# Fri3d_2026_Keeb_01.net
KiCad netlist of a schematic drawn in Altium Designer
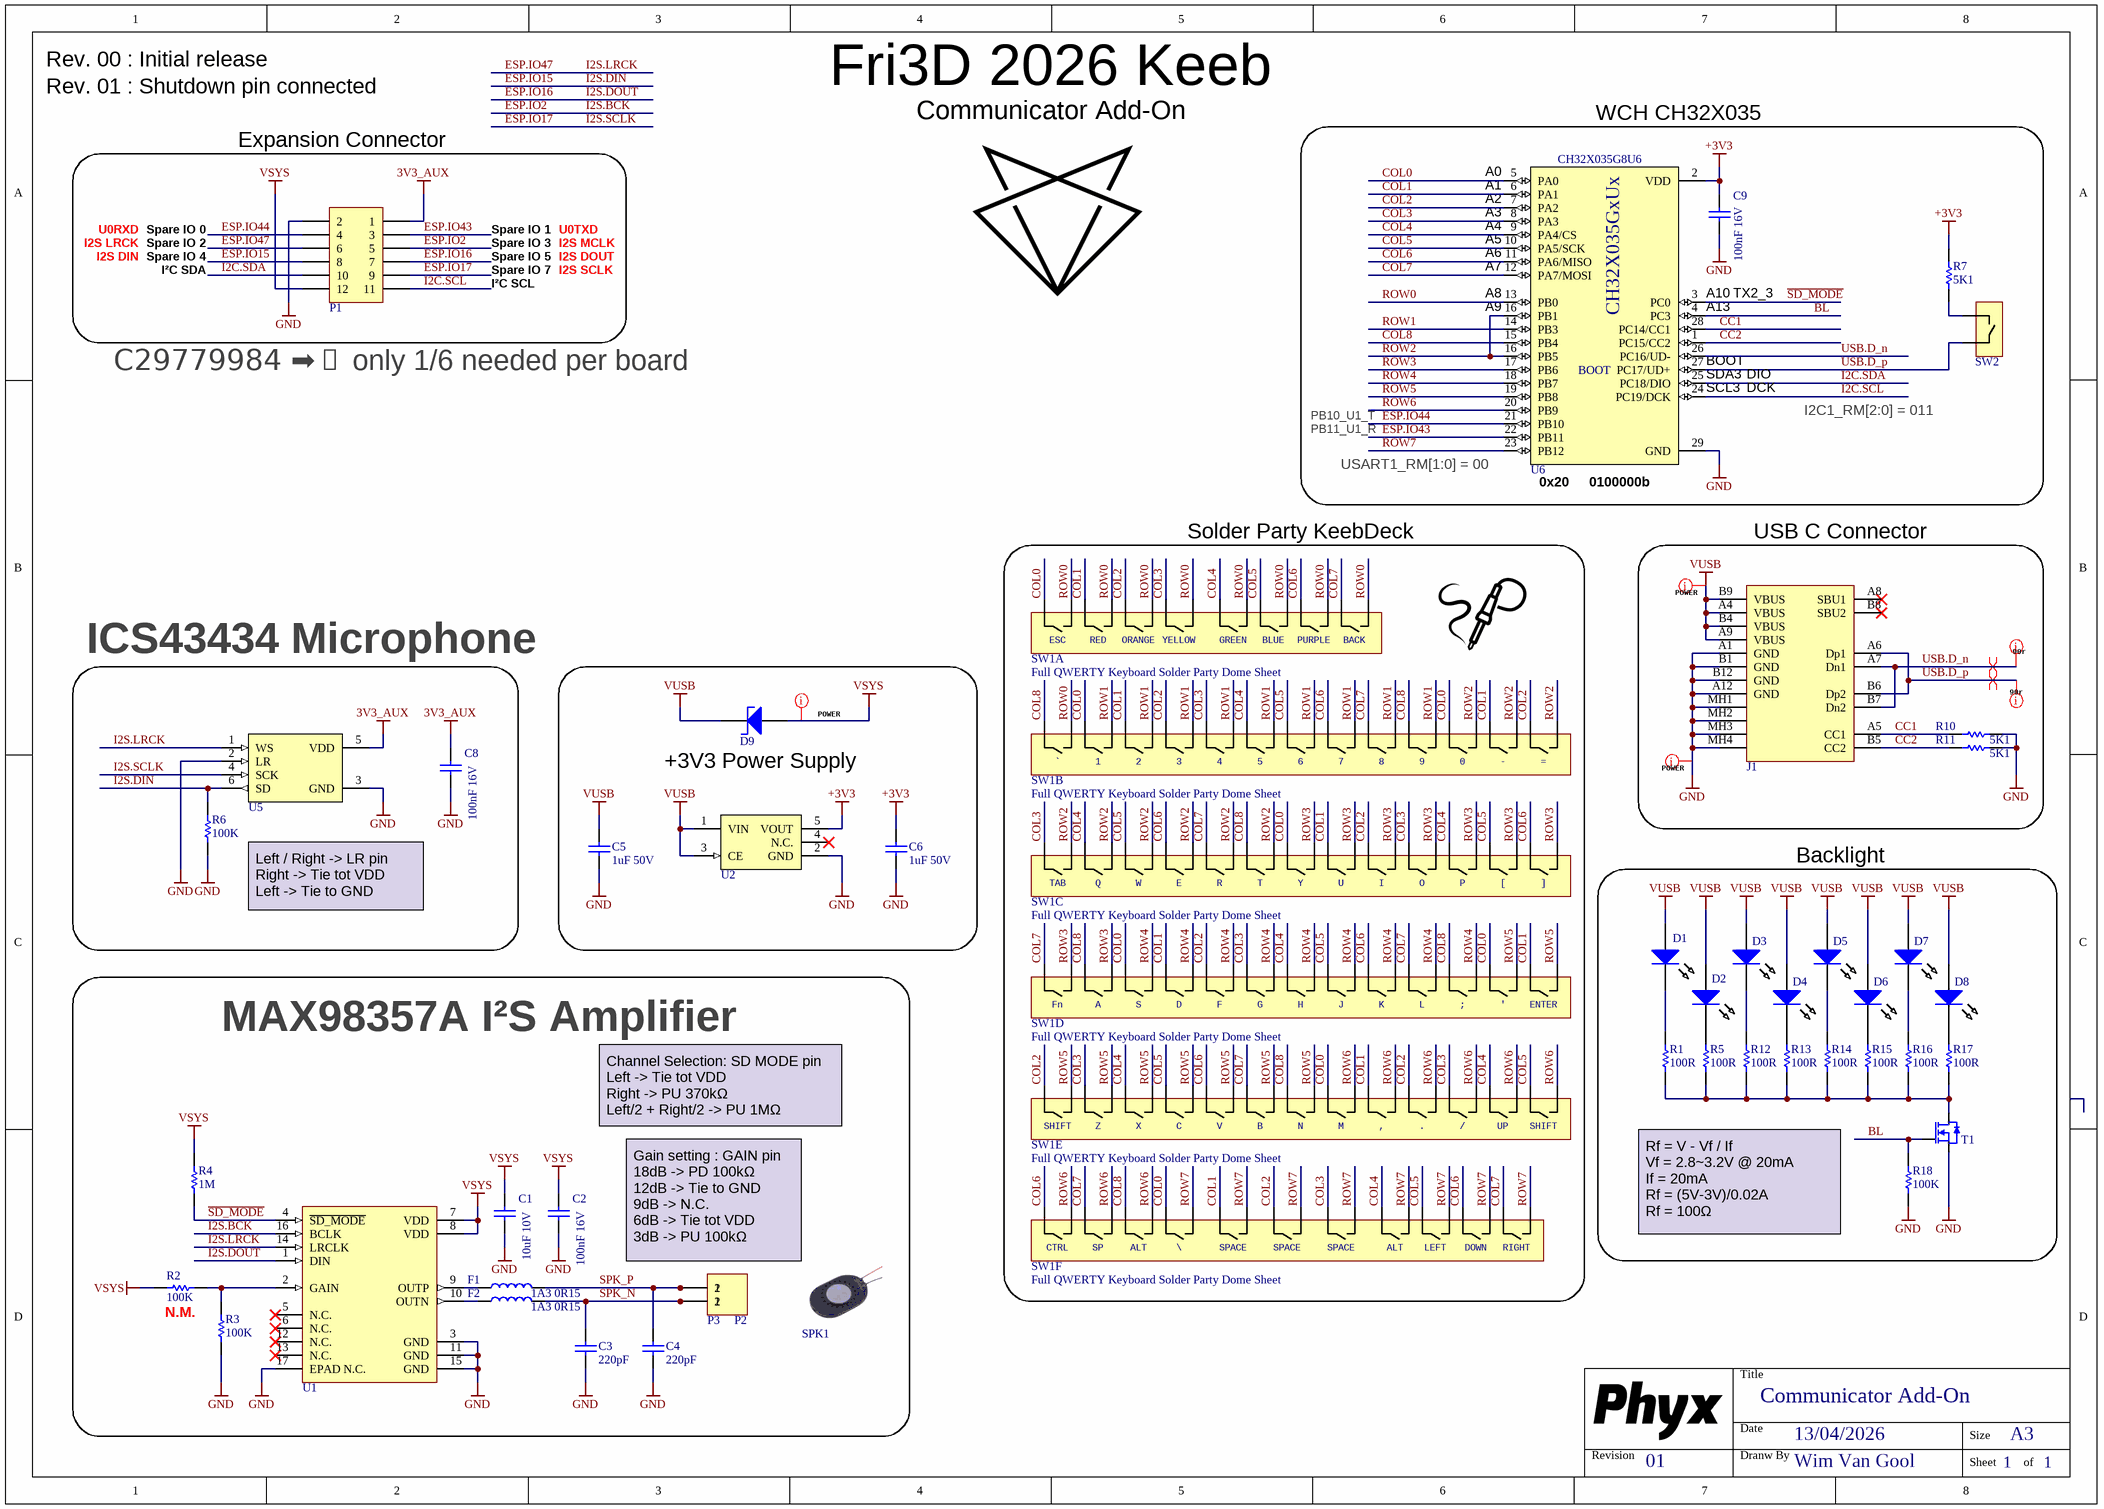
[diagram p0: Fri3d_2026_Keeb_01.SchDoc]

(export (version "E")
  (design (tool "Eeschema 10.0.6"))
  (components
    (comp (ref "C1")
      (value "10uF 10V")
      (footprint "C0805_N")
      (description "Capacitor Ceramic")
      (fields (field (name "Comment") "CAP_CERAMIC"))
      (libsource (lib "Phyx_Components") (part "CAP_CERAMIC"))
    )
    (comp (ref "C2")
      (value "100nF 16V")
      (footprint "C0603_N")
      (description "Capacitor Ceramic")
      (libsource (lib "Phyx_Components") (part "CAP_CERAMIC"))
    )
    (comp (ref "C3")
      (value "220pF")
      (footprint "C0603_N")
      (description "Capacitor Ceramic")
      (fields (field (name "Comment") "CAP_CERAMIC"))
      (libsource (lib "Phyx_Components") (part "CAP_CERAMIC"))
    )
    (comp (ref "C4")
      (value "220pF")
      (footprint "C0603_N")
      (description "Capacitor Ceramic")
      (fields (field (name "Comment") "CAP_CERAMIC"))
      (libsource (lib "Phyx_Components") (part "CAP_CERAMIC"))
    )
    (comp (ref "C5")
      (value "1uF 50V")
      (footprint "C0603_N")
      (description "Capacitor Ceramic")
      (fields (field (name "Comment") "CAP_CERAMIC"))
      (libsource (lib "Phyx_Components") (part "CAP_CERAMIC"))
    )
    (comp (ref "C6")
      (value "1uF 50V")
      (footprint "C0603_N")
      (description "Capacitor Ceramic")
      (fields (field (name "Comment") "CAP_CERAMIC"))
      (libsource (lib "Phyx_Components") (part "CAP_CERAMIC"))
    )
    (comp (ref "C8")
      (value "100nF 16V")
      (footprint "C0603_N")
      (description "Capacitor Ceramic")
      (libsource (lib "Phyx_Components") (part "CAP_CERAMIC"))
    )
    (comp (ref "C9")
      (value "100nF 16V")
      (footprint "C0603_N")
      (description "Capacitor Ceramic")
      (libsource (lib "Phyx_Components") (part "CAP_CERAMIC"))
    )
    (comp (ref "D1")
      (value "Side emitting Cool White LED 3.0V 30mA 120° 2900mcd")
      (footprint "LITE_LTW-010DCG")
      (description "=Description")
      (libsource (lib "Phyx_Components") (part "LED_WHITE"))
    )
    (comp (ref "D2")
      (value "Side emitting Cool White LED 3.0V 30mA 120° 2900mcd")
      (footprint "LITE_LTW-010DCG")
      (description "=Description")
      (libsource (lib "Phyx_Components") (part "LED_WHITE"))
    )
    (comp (ref "D3")
      (value "Side emitting Cool White LED 3.0V 30mA 120° 2900mcd")
      (footprint "LITE_LTW-010DCG")
      (description "=Description")
      (libsource (lib "Phyx_Components") (part "LED_WHITE"))
    )
    (comp (ref "D4")
      (value "Side emitting Cool White LED 3.0V 30mA 120° 2900mcd")
      (footprint "LITE_LTW-010DCG")
      (description "=Description")
      (libsource (lib "Phyx_Components") (part "LED_WHITE"))
    )
    (comp (ref "D5")
      (value "Side emitting Cool White LED 3.0V 30mA 120° 2900mcd")
      (footprint "LITE_LTW-010DCG")
      (description "=Description")
      (libsource (lib "Phyx_Components") (part "LED_WHITE"))
    )
    (comp (ref "D6")
      (value "Side emitting Cool White LED 3.0V 30mA 120° 2900mcd")
      (footprint "LITE_LTW-010DCG")
      (description "=Description")
      (libsource (lib "Phyx_Components") (part "LED_WHITE"))
    )
    (comp (ref "D7")
      (value "Side emitting Cool White LED 3.0V 30mA 120° 2900mcd")
      (footprint "LITE_LTW-010DCG")
      (description "=Description")
      (libsource (lib "Phyx_Components") (part "LED_WHITE"))
    )
    (comp (ref "D8")
      (value "Side emitting Cool White LED 3.0V 30mA 120° 2900mcd")
      (footprint "LITE_LTW-010DCG")
      (description "=Description")
      (libsource (lib "Phyx_Components") (part "LED_WHITE"))
    )
    (comp (ref "D9")
      (value "CUS10S30 Schottky Power Rectifier, 1A, 30V")
      (footprint "SOD-323_AC")
      (description "=Description")
      (libsource (lib "Phyx_Components") (part "Schottky_AC"))
    )
    (comp (ref "F1")
      (value "1A3 0R15")
      (footprint "L0603")
      (fields (field (name "Comment") "BLM18KG601SN1D"))
      (libsource (lib "Phyx_Components") (part "FERRITE"))
    )
    (comp (ref "F2")
      (value "1A3 0R15")
      (footprint "L0603")
      (fields (field (name "Comment") "BLM18KG601SN1D"))
      (libsource (lib "Phyx_Components") (part "FERRITE"))
    )
    (comp (ref "J1")
      (value "USB 2.0 C Reversible Receptacle Horizontal full SMD")
      (footprint "XUNPU-TYPEC-304S-ACP16")
      (libsource (lib "Phyx_Components") (part "USB_C_16_4"))
    )
    (comp (ref "P1")
      (value "Header 6X2")
      (footprint "HDR2X6")
      (libsource (lib "Phyx_Components") (part "Header 6X2"))
    )
    (comp (ref "P2")
      (value "SHETIME WAF02-T1T1-2021-D")
      (footprint "SHE_WAF02-T1T1-2021-D")
      (libsource (lib "Phyx_Components") (part "Header 2"))
    )
    (comp (ref "P3") (value "Header 2 RA") (footprint "HDR1X2_RA") (libsource (lib "") (part "Header 2_1")))
    (comp (ref "R1")
      (value "100R")
      (footprint "R0603_N")
      (fields (field (name "Comment") "RESISTOR"))
      (libsource (lib "Phyx_Components") (part "RESISTOR"))
    )
    (comp (ref "R2")
      (value "100K")
      (footprint "R0603_N")
      (fields (field (name "Comment") "RESISTOR"))
      (libsource (lib "Phyx_Components") (part "RESISTOR"))
    )
    (comp (ref "R3")
      (value "100K")
      (footprint "R0603_N")
      (fields (field (name "Comment") "RESISTOR"))
      (libsource (lib "Phyx_Components") (part "RESISTOR"))
    )
    (comp (ref "R4")
      (value "1M")
      (footprint "R0603_N")
      (fields (field (name "Comment") "RESISTOR"))
      (libsource (lib "Phyx_Components") (part "RESISTOR"))
    )
    (comp (ref "R5")
      (value "100R")
      (footprint "R0603_N")
      (fields (field (name "Comment") "RESISTOR"))
      (libsource (lib "Phyx_Components") (part "RESISTOR"))
    )
    (comp (ref "R6")
      (value "100K")
      (footprint "R0603_N")
      (fields (field (name "Comment") "RESISTOR"))
      (libsource (lib "Phyx_Components") (part "RESISTOR"))
    )
    (comp (ref "R7")
      (value "5K1")
      (footprint "R0603_N")
      (fields (field (name "Comment") "RESISTOR"))
      (libsource (lib "Phyx_Components") (part "RESISTOR"))
    )
    (comp (ref "R10")
      (value "5K1")
      (footprint "R0603_N")
      (fields (field (name "Comment") "RESISTOR"))
      (libsource (lib "Phyx_Components") (part "RESISTOR"))
    )
    (comp (ref "R11")
      (value "5K1")
      (footprint "R0603_N")
      (fields (field (name "Comment") "RESISTOR"))
      (libsource (lib "Phyx_Components") (part "RESISTOR"))
    )
    (comp (ref "R12")
      (value "100R")
      (footprint "R0603_N")
      (fields (field (name "Comment") "RESISTOR"))
      (libsource (lib "Phyx_Components") (part "RESISTOR"))
    )
    (comp (ref "R13")
      (value "100R")
      (footprint "R0603_N")
      (fields (field (name "Comment") "RESISTOR"))
      (libsource (lib "Phyx_Components") (part "RESISTOR"))
    )
    (comp (ref "R14")
      (value "100R")
      (footprint "R0603_N")
      (fields (field (name "Comment") "RESISTOR"))
      (libsource (lib "Phyx_Components") (part "RESISTOR"))
    )
    (comp (ref "R15")
      (value "100R")
      (footprint "R0603_N")
      (fields (field (name "Comment") "RESISTOR"))
      (libsource (lib "Phyx_Components") (part "RESISTOR"))
    )
    (comp (ref "R16")
      (value "100R")
      (footprint "R0603_N")
      (fields (field (name "Comment") "RESISTOR"))
      (libsource (lib "Phyx_Components") (part "RESISTOR"))
    )
    (comp (ref "R17")
      (value "100R")
      (footprint "R0603_N")
      (fields (field (name "Comment") "RESISTOR"))
      (libsource (lib "Phyx_Components") (part "RESISTOR"))
    )
    (comp (ref "R18")
      (value "100K")
      (footprint "R0603_N")
      (fields (field (name "Comment") "RESISTOR"))
      (libsource (lib "Phyx_Components") (part "RESISTOR"))
    )
    (comp (ref "SPK1")
      (value "INGHAi GSPK3020035PN 8R 1W 100mm Leads")
      (libsource (lib "Phyx_Components") (part "GSPK3020035PN"))
    )
    (comp (ref "SW1")
      (value "Full QWERTY Keyboard Solder Party Dome Sheet")
      (footprint "Solder_Party_Keyb")
      (libsource (lib "CONNECTORS") (part "Solder_Party_Keyb"))
    )
    (comp (ref "SW2")
      (value "4.5x4.5mm tact SMD H3,8mm")
      (footprint "WE_430181038816")
      (libsource (lib "Phyx_Components") (part "SW_TACT"))
    )
    (comp (ref "T1")
      (value "0.2A N-Ch MOSFET Vgs 1.5")
      (footprint "SOT23-3")
      (libsource (lib "Phyx_Components") (part "N_MOSFET_GSD"))
    )
    (comp (ref "U1")
      (value "Mono I²S DAC AMP 3W 2.5~5.5V")
      (footprint "QFN_16_0.5_3X3")
      (description "=Description")
      (libsource (lib "Phyx_Components") (part "ADI_MAX98357_QFN"))
    )
    (comp (ref "U2")
      (value "3V3 LDO 300mA 150mV")
      (footprint "SOT23-5")
      (description "=Designator")
      (libsource (lib "Phyx_Components") (part "XC6210_SOT"))
    )
    (comp (ref "U5")
      (value "I2S MIC ICS-43434")
      (footprint "TDK_ICS-43434")
      (description "=Description")
      (libsource (lib "Phyx_Components") (part "TDK_ICS-43434"))
    )
    (comp (ref "U6")
      (value "CH32X035G8U6")
      (footprint "QFN_28_4.0x4.0_P0.4")
      (fields
        (field (name "Comment") "WCH CH32X035G8U6 QFN28 RISC-V 32-bit MCU, 62KB Flash, 10KB RAM, USB PD")
      )
      (libsource (lib "Phyx_Components") (part "WCH_CH32X035GxUx"))
    )
  )
  (nets
    (net (code "1") (name "+3V3") (class "Default")
      (node (ref "C6") (pin "1") (pinfunction "1_1") (pintype "passive"))
      (node (ref "C9") (pin "1") (pinfunction "1_1") (pintype "passive"))
      (node (ref "R7") (pin "1") (pinfunction "1_1") (pintype "passive"))
      (node (ref "U2") (pin "5") (pinfunction "VOUT_5") (pintype "power_in"))
      (node (ref "U6") (pin "2") (pinfunction "VDD_2") (pintype "power_in"))
    )
    (net (code "2") (name "/BL") (class "Default")
      (node (ref "R18") (pin "1") (pinfunction "1_1") (pintype "passive"))
      (node (ref "T1") (pin "1") (pinfunction "G_1") (pintype "passive"))
      (node (ref "U6") (pin "4") (pinfunction "PC3_4") (pintype "bidirectional"))
    )
    (net (code "3") (name "/CC1") (class "Default")
      (node (ref "J1") (pin "A5") (pinfunction "CC1_A5") (pintype "passive"))
      (node (ref "R10") (pin "1") (pinfunction "1_1") (pintype "passive"))
      (node (ref "U6") (pin "28") (pinfunction "PC14/CC1_28") (pintype "bidirectional"))
    )
    (net (code "4") (name "/CC2") (class "Default")
      (node (ref "J1") (pin "B5") (pinfunction "CC2_B5") (pintype "passive"))
      (node (ref "R11") (pin "1") (pinfunction "1_1") (pintype "passive"))
      (node (ref "U6") (pin "1") (pinfunction "PC15/CC2_1") (pintype "bidirectional"))
    )
    (net (code "5") (name "/COL0") (class "Default")
      (node (ref "SW1") (pin "1") (pinfunction "1_1") (pintype "passive"))
      (node (ref "SW1") (pin "109") (pinfunction "109_109") (pintype "passive"))
      (node (ref "SW1") (pin "127") (pinfunction "127_127") (pintype "passive"))
      (node (ref "SW1") (pin "19") (pinfunction "19_19") (pintype "passive"))
      (node (ref "SW1") (pin "37") (pinfunction "37_37") (pintype "passive"))
      (node (ref "SW1") (pin "55") (pinfunction "55_55") (pintype "passive"))
      (node (ref "SW1") (pin "73") (pinfunction "73_73") (pintype "passive"))
      (node (ref "SW1") (pin "91") (pinfunction "91_91") (pintype "passive"))
      (node (ref "U6") (pin "5") (pinfunction "PA0_5") (pintype "bidirectional"))
    )
    (net (code "6") (name "/COL1") (class "Default")
      (node (ref "SW1") (pin "111") (pinfunction "111_111") (pintype "passive"))
      (node (ref "SW1") (pin "129") (pinfunction "129_129") (pintype "passive"))
      (node (ref "SW1") (pin "21") (pinfunction "21_21") (pintype "passive"))
      (node (ref "SW1") (pin "3") (pinfunction "3_3") (pintype "passive"))
      (node (ref "SW1") (pin "39") (pinfunction "39_39") (pintype "passive"))
      (node (ref "SW1") (pin "57") (pinfunction "57_57") (pintype "passive"))
      (node (ref "SW1") (pin "75") (pinfunction "75_75") (pintype "passive"))
      (node (ref "SW1") (pin "93") (pinfunction "93_93") (pintype "passive"))
      (node (ref "U6") (pin "6") (pinfunction "PA1_6") (pintype "bidirectional"))
    )
    (net (code "7") (name "/COL2") (class "Default")
      (node (ref "SW1") (pin "113") (pinfunction "113_113") (pintype "passive"))
      (node (ref "SW1") (pin "131") (pinfunction "131_131") (pintype "passive"))
      (node (ref "SW1") (pin "23") (pinfunction "23_23") (pintype "passive"))
      (node (ref "SW1") (pin "41") (pinfunction "41_41") (pintype "passive"))
      (node (ref "SW1") (pin "5") (pinfunction "5_5") (pintype "passive"))
      (node (ref "SW1") (pin "59") (pinfunction "59_59") (pintype "passive"))
      (node (ref "SW1") (pin "77") (pinfunction "77_77") (pintype "passive"))
      (node (ref "SW1") (pin "95") (pinfunction "95_95") (pintype "passive"))
      (node (ref "U6") (pin "7") (pinfunction "PA2_7") (pintype "bidirectional"))
    )
    (net (code "8") (name "/COL3") (class "Default")
      (node (ref "SW1") (pin "115") (pinfunction "115_115") (pintype "passive"))
      (node (ref "SW1") (pin "133") (pinfunction "133_133") (pintype "passive"))
      (node (ref "SW1") (pin "25") (pinfunction "25_25") (pintype "passive"))
      (node (ref "SW1") (pin "43") (pinfunction "43_43") (pintype "passive"))
      (node (ref "SW1") (pin "61") (pinfunction "61_61") (pintype "passive"))
      (node (ref "SW1") (pin "7") (pinfunction "7_7") (pintype "passive"))
      (node (ref "SW1") (pin "79") (pinfunction "79_79") (pintype "passive"))
      (node (ref "SW1") (pin "97") (pinfunction "97_97") (pintype "passive"))
      (node (ref "U6") (pin "8") (pinfunction "PA3_8") (pintype "bidirectional"))
    )
    (net (code "9") (name "/COL4") (class "Default")
      (node (ref "SW1") (pin "117") (pinfunction "117_117") (pintype "passive"))
      (node (ref "SW1") (pin "135") (pinfunction "135_135") (pintype "passive"))
      (node (ref "SW1") (pin "27") (pinfunction "27_27") (pintype "passive"))
      (node (ref "SW1") (pin "45") (pinfunction "45_45") (pintype "passive"))
      (node (ref "SW1") (pin "63") (pinfunction "63_63") (pintype "passive"))
      (node (ref "SW1") (pin "81") (pinfunction "81_81") (pintype "passive"))
      (node (ref "SW1") (pin "9") (pinfunction "9_9") (pintype "passive"))
      (node (ref "SW1") (pin "99") (pinfunction "99_99") (pintype "passive"))
      (node (ref "U6") (pin "9") (pinfunction "PA4/CS_9") (pintype "bidirectional"))
    )
    (net (code "10") (name "/COL5") (class "Default")
      (node (ref "SW1") (pin "101") (pinfunction "101_101") (pintype "passive"))
      (node (ref "SW1") (pin "11") (pinfunction "11_11") (pintype "passive"))
      (node (ref "SW1") (pin "119") (pinfunction "119_119") (pintype "passive"))
      (node (ref "SW1") (pin "137") (pinfunction "137_137") (pintype "passive"))
      (node (ref "SW1") (pin "29") (pinfunction "29_29") (pintype "passive"))
      (node (ref "SW1") (pin "47") (pinfunction "47_47") (pintype "passive"))
      (node (ref "SW1") (pin "65") (pinfunction "65_65") (pintype "passive"))
      (node (ref "SW1") (pin "83") (pinfunction "83_83") (pintype "passive"))
      (node (ref "U6") (pin "10") (pinfunction "PA5/SCK_10") (pintype "bidirectional"))
    )
    (net (code "11") (name "/COL6") (class "Default")
      (node (ref "SW1") (pin "103") (pinfunction "103_103") (pintype "passive"))
      (node (ref "SW1") (pin "121") (pinfunction "121_121") (pintype "passive"))
      (node (ref "SW1") (pin "13") (pinfunction "13_13") (pintype "passive"))
      (node (ref "SW1") (pin "139") (pinfunction "139_139") (pintype "passive"))
      (node (ref "SW1") (pin "31") (pinfunction "31_31") (pintype "passive"))
      (node (ref "SW1") (pin "49") (pinfunction "49_49") (pintype "passive"))
      (node (ref "SW1") (pin "67") (pinfunction "67_67") (pintype "passive"))
      (node (ref "SW1") (pin "85") (pinfunction "85_85") (pintype "passive"))
      (node (ref "U6") (pin "11") (pinfunction "PA6/MISO_11") (pintype "bidirectional"))
    )
    (net (code "12") (name "/COL7") (class "Default")
      (node (ref "SW1") (pin "105") (pinfunction "105_105") (pintype "passive"))
      (node (ref "SW1") (pin "123") (pinfunction "123_123") (pintype "passive"))
      (node (ref "SW1") (pin "141") (pinfunction "141_141") (pintype "passive"))
      (node (ref "SW1") (pin "15") (pinfunction "15_15") (pintype "passive"))
      (node (ref "SW1") (pin "33") (pinfunction "33_33") (pintype "passive"))
      (node (ref "SW1") (pin "51") (pinfunction "51_51") (pintype "passive"))
      (node (ref "SW1") (pin "69") (pinfunction "69_69") (pintype "passive"))
      (node (ref "SW1") (pin "87") (pinfunction "87_87") (pintype "passive"))
      (node (ref "U6") (pin "12") (pinfunction "PA7/MOSI_12") (pintype "bidirectional"))
    )
    (net (code "13") (name "/COL8") (class "Default")
      (node (ref "SW1") (pin "107") (pinfunction "107_107") (pintype "passive"))
      (node (ref "SW1") (pin "125") (pinfunction "125_125") (pintype "passive"))
      (node (ref "SW1") (pin "17") (pinfunction "17_17") (pintype "passive"))
      (node (ref "SW1") (pin "35") (pinfunction "35_35") (pintype "passive"))
      (node (ref "SW1") (pin "53") (pinfunction "53_53") (pintype "passive"))
      (node (ref "SW1") (pin "71") (pinfunction "71_71") (pintype "passive"))
      (node (ref "SW1") (pin "89") (pinfunction "89_89") (pintype "passive"))
      (node (ref "U6") (pin "15") (pinfunction "PB4_15") (pintype "bidirectional"))
    )
    (net (code "14") (name "/ESP.IO2") (class "Default")
      (node (ref "P1") (pin "5") (pinfunction "5_5") (pintype "passive"))
      (node (ref "U1") (pin "16") (pinfunction "BCLK_16") (pintype "input"))
    )
    (net (code "15") (name "/ESP.IO15") (class "Default")
      (node (ref "P1") (pin "8") (pinfunction "8_8") (pintype "passive"))
      (node (ref "R6") (pin "1") (pinfunction "1_1") (pintype "passive"))
      (node (ref "U5") (pin "6") (pinfunction "SD_6") (pintype "output"))
    )
    (net (code "16") (name "/ESP.IO16") (class "Default")
      (node (ref "P1") (pin "7") (pinfunction "7_7") (pintype "passive"))
      (node (ref "U1") (pin "1") (pinfunction "DIN_1") (pintype "input"))
    )
    (net (code "17") (name "/ESP.IO17") (class "Default")
      (node (ref "P1") (pin "9") (pinfunction "9_9") (pintype "passive"))
      (node (ref "U5") (pin "4") (pinfunction "SCK_4") (pintype "input"))
    )
    (net (code "18") (name "/ESP.IO43") (class "Default")
      (node (ref "P1") (pin "3") (pinfunction "3_3") (pintype "passive"))
      (node (ref "U6") (pin "22") (pinfunction "PB11_22") (pintype "bidirectional"))
    )
    (net (code "19") (name "/ESP.IO44") (class "Default")
      (node (ref "P1") (pin "4") (pinfunction "4_4") (pintype "passive"))
      (node (ref "U6") (pin "21") (pinfunction "PB10_21") (pintype "bidirectional"))
    )
    (net (code "20") (name "/ESP.IO47") (class "Default")
      (node (ref "P1") (pin "6") (pinfunction "6_6") (pintype "passive"))
      (node (ref "U1") (pin "14") (pinfunction "LRCLK_14") (pintype "input"))
      (node (ref "U5") (pin "1") (pinfunction "WS_1") (pintype "input"))
    )
    (net (code "21") (name "/I2C.SCL") (class "Default")
      (node (ref "P1") (pin "11") (pinfunction "11_11") (pintype "passive"))
      (node (ref "U6") (pin "24") (pinfunction "PC19/DCK_24") (pintype "bidirectional"))
    )
    (net (code "22") (name "/I2C.SDA") (class "Default")
      (node (ref "P1") (pin "10") (pinfunction "10_10") (pintype "passive"))
      (node (ref "U6") (pin "25") (pinfunction "PC18/DIO_25") (pintype "bidirectional"))
    )
    (net (code "23") (name "/ROW0") (class "Default")
      (node (ref "SW1") (pin "10") (pinfunction "10_10") (pintype "passive"))
      (node (ref "SW1") (pin "12") (pinfunction "12_12") (pintype "passive"))
      (node (ref "SW1") (pin "14") (pinfunction "14_14") (pintype "passive"))
      (node (ref "SW1") (pin "16") (pinfunction "16_16") (pintype "passive"))
      (node (ref "SW1") (pin "18") (pinfunction "18_18") (pintype "passive"))
      (node (ref "SW1") (pin "2") (pinfunction "2_2") (pintype "passive"))
      (node (ref "SW1") (pin "4") (pinfunction "4_4") (pintype "passive"))
      (node (ref "SW1") (pin "6") (pinfunction "6_6") (pintype "passive"))
      (node (ref "SW1") (pin "8") (pinfunction "8_8") (pintype "passive"))
      (node (ref "U6") (pin "13") (pinfunction "PB0_13") (pintype "bidirectional"))
    )
    (net (code "24") (name "/ROW1") (class "Default")
      (node (ref "SW1") (pin "20") (pinfunction "20_20") (pintype "passive"))
      (node (ref "SW1") (pin "22") (pinfunction "22_22") (pintype "passive"))
      (node (ref "SW1") (pin "24") (pinfunction "24_24") (pintype "passive"))
      (node (ref "SW1") (pin "26") (pinfunction "26_26") (pintype "passive"))
      (node (ref "SW1") (pin "28") (pinfunction "28_28") (pintype "passive"))
      (node (ref "SW1") (pin "30") (pinfunction "30_30") (pintype "passive"))
      (node (ref "SW1") (pin "32") (pinfunction "32_32") (pintype "passive"))
      (node (ref "SW1") (pin "34") (pinfunction "34_34") (pintype "passive"))
      (node (ref "SW1") (pin "36") (pinfunction "36_36") (pintype "passive"))
      (node (ref "U6") (pin "14") (pinfunction "PB3_14") (pintype "bidirectional"))
    )
    (net (code "25") (name "/ROW2") (class "Default")
      (node (ref "SW1") (pin "38") (pinfunction "38_38") (pintype "passive"))
      (node (ref "SW1") (pin "40") (pinfunction "40_40") (pintype "passive"))
      (node (ref "SW1") (pin "42") (pinfunction "42_42") (pintype "passive"))
      (node (ref "SW1") (pin "44") (pinfunction "44_44") (pintype "passive"))
      (node (ref "SW1") (pin "46") (pinfunction "46_46") (pintype "passive"))
      (node (ref "SW1") (pin "48") (pinfunction "48_48") (pintype "passive"))
      (node (ref "SW1") (pin "50") (pinfunction "50_50") (pintype "passive"))
      (node (ref "SW1") (pin "52") (pinfunction "52_52") (pintype "passive"))
      (node (ref "SW1") (pin "54") (pinfunction "54_54") (pintype "passive"))
      (node (ref "U6") (pin "16") (pinfunction "PB1_16") (pintype "bidirectional"))
    )
    (net (code "26") (name "/ROW3") (class "Default")
      (node (ref "SW1") (pin "56") (pinfunction "56_56") (pintype "passive"))
      (node (ref "SW1") (pin "58") (pinfunction "58_58") (pintype "passive"))
      (node (ref "SW1") (pin "60") (pinfunction "60_60") (pintype "passive"))
      (node (ref "SW1") (pin "62") (pinfunction "62_62") (pintype "passive"))
      (node (ref "SW1") (pin "64") (pinfunction "64_64") (pintype "passive"))
      (node (ref "SW1") (pin "66") (pinfunction "66_66") (pintype "passive"))
      (node (ref "SW1") (pin "68") (pinfunction "68_68") (pintype "passive"))
      (node (ref "SW1") (pin "70") (pinfunction "70_70") (pintype "passive"))
      (node (ref "SW1") (pin "72") (pinfunction "72_72") (pintype "passive"))
      (node (ref "U6") (pin "17") (pinfunction "PB6_17") (pintype "bidirectional"))
    )
    (net (code "27") (name "/ROW4") (class "Default")
      (node (ref "SW1") (pin "74") (pinfunction "74_74") (pintype "passive"))
      (node (ref "SW1") (pin "76") (pinfunction "76_76") (pintype "passive"))
      (node (ref "SW1") (pin "78") (pinfunction "78_78") (pintype "passive"))
      (node (ref "SW1") (pin "80") (pinfunction "80_80") (pintype "passive"))
      (node (ref "SW1") (pin "82") (pinfunction "82_82") (pintype "passive"))
      (node (ref "SW1") (pin "84") (pinfunction "84_84") (pintype "passive"))
      (node (ref "SW1") (pin "86") (pinfunction "86_86") (pintype "passive"))
      (node (ref "SW1") (pin "88") (pinfunction "88_88") (pintype "passive"))
      (node (ref "SW1") (pin "90") (pinfunction "90_90") (pintype "passive"))
      (node (ref "U6") (pin "18") (pinfunction "PB7_18") (pintype "bidirectional"))
    )
    (net (code "28") (name "/ROW5") (class "Default")
      (node (ref "SW1") (pin "100") (pinfunction "100_100") (pintype "passive"))
      (node (ref "SW1") (pin "102") (pinfunction "102_102") (pintype "passive"))
      (node (ref "SW1") (pin "104") (pinfunction "104_104") (pintype "passive"))
      (node (ref "SW1") (pin "106") (pinfunction "106_106") (pintype "passive"))
      (node (ref "SW1") (pin "108") (pinfunction "108_108") (pintype "passive"))
      (node (ref "SW1") (pin "92") (pinfunction "92_92") (pintype "passive"))
      (node (ref "SW1") (pin "94") (pinfunction "94_94") (pintype "passive"))
      (node (ref "SW1") (pin "96") (pinfunction "96_96") (pintype "passive"))
      (node (ref "SW1") (pin "98") (pinfunction "98_98") (pintype "passive"))
      (node (ref "U6") (pin "19") (pinfunction "PB8_19") (pintype "bidirectional"))
    )
    (net (code "29") (name "/ROW6") (class "Default")
      (node (ref "SW1") (pin "110") (pinfunction "110_110") (pintype "passive"))
      (node (ref "SW1") (pin "112") (pinfunction "112_112") (pintype "passive"))
      (node (ref "SW1") (pin "114") (pinfunction "114_114") (pintype "passive"))
      (node (ref "SW1") (pin "116") (pinfunction "116_116") (pintype "passive"))
      (node (ref "SW1") (pin "118") (pinfunction "118_118") (pintype "passive"))
      (node (ref "SW1") (pin "120") (pinfunction "120_120") (pintype "passive"))
      (node (ref "SW1") (pin "122") (pinfunction "122_122") (pintype "passive"))
      (node (ref "SW1") (pin "124") (pinfunction "124_124") (pintype "passive"))
      (node (ref "SW1") (pin "126") (pinfunction "126_126") (pintype "passive"))
      (node (ref "U6") (pin "20") (pinfunction "PB9_20") (pintype "bidirectional"))
    )
    (net (code "30") (name "/ROW7") (class "Default")
      (node (ref "SW1") (pin "128") (pinfunction "128_128") (pintype "passive"))
      (node (ref "SW1") (pin "130") (pinfunction "130_130") (pintype "passive"))
      (node (ref "SW1") (pin "132") (pinfunction "132_132") (pintype "passive"))
      (node (ref "SW1") (pin "134") (pinfunction "134_134") (pintype "passive"))
      (node (ref "SW1") (pin "136") (pinfunction "136_136") (pintype "passive"))
      (node (ref "SW1") (pin "138") (pinfunction "138_138") (pintype "passive"))
      (node (ref "SW1") (pin "140") (pinfunction "140_140") (pintype "passive"))
      (node (ref "SW1") (pin "142") (pinfunction "142_142") (pintype "passive"))
      (node (ref "U6") (pin "23") (pinfunction "PB12_23") (pintype "bidirectional"))
    )
    (net (code "31") (name "/SPK_N") (class "Default")
      (node (ref "C3") (pin "1") (pinfunction "1_1") (pintype "passive"))
      (node (ref "F2") (pin "2") (pinfunction "2_2") (pintype "passive"))
      (node (ref "P2") (pin "2") (pinfunction "2_2") (pintype "passive"))
      (node (ref "P3") (pin "1") (pinfunction "1_1") (pintype "passive"))
    )
    (net (code "32") (name "/SPK_P") (class "Default")
      (node (ref "C4") (pin "1") (pinfunction "1_1") (pintype "passive"))
      (node (ref "F1") (pin "2") (pinfunction "2_2") (pintype "passive"))
      (node (ref "P2") (pin "1") (pinfunction "1_1") (pintype "passive"))
      (node (ref "P3") (pin "2") (pinfunction "2_2") (pintype "passive"))
    )
    (net (code "33") (name "/USB.D_n") (class "Default")
      (node (ref "J1") (pin "A7") (pinfunction "Dn1_A7") (pintype "passive"))
      (node (ref "J1") (pin "B7") (pinfunction "Dn2_B7") (pintype "passive"))
      (node (ref "U6") (pin "26") (pinfunction "PC16/UD-_26") (pintype "bidirectional"))
    )
    (net (code "34") (name "/USB.D_p") (class "Default")
      (node (ref "J1") (pin "A6") (pinfunction "Dp1_A6") (pintype "passive"))
      (node (ref "J1") (pin "B6") (pinfunction "Dp2_B6") (pintype "passive"))
      (node (ref "SW2") (pin "2") (pinfunction "2_2") (pintype "passive"))
      (node (ref "U6") (pin "27") (pinfunction "PC17/UD+_27") (pintype "bidirectional"))
    )
    (net (code "35") (name "/~{SD_MODE}") (class "Default")
      (node (ref "R4") (pin "2") (pinfunction "2_2") (pintype "passive"))
      (node (ref "U1") (pin "4") (pinfunction "~{SD_MODE}_4") (pintype "input"))
      (node (ref "U6") (pin "3") (pinfunction "PC0_3") (pintype "bidirectional"))
    )
    (net (code "36") (name "3V3_AUX") (class "Default")
      (node (ref "C8") (pin "1") (pinfunction "1_1") (pintype "passive"))
      (node (ref "P1") (pin "1") (pinfunction "1_1") (pintype "passive"))
      (node (ref "U5") (pin "5") (pinfunction "VDD_5") (pintype "power_in"))
    )
    (net (code "37") (name "GND") (class "Default")
      (node (ref "C1") (pin "2") (pinfunction "2_2") (pintype "passive"))
      (node (ref "C2") (pin "2") (pinfunction "2_2") (pintype "passive"))
      (node (ref "C3") (pin "2") (pinfunction "2_2") (pintype "passive"))
      (node (ref "C4") (pin "2") (pinfunction "2_2") (pintype "passive"))
      (node (ref "C5") (pin "2") (pinfunction "2_2") (pintype "passive"))
      (node (ref "C6") (pin "2") (pinfunction "2_2") (pintype "passive"))
      (node (ref "C8") (pin "2") (pinfunction "2_2") (pintype "passive"))
      (node (ref "C9") (pin "2") (pinfunction "2_2") (pintype "passive"))
      (node (ref "J1") (pin "A1") (pinfunction "GND_A1") (pintype "passive"))
      (node (ref "J1") (pin "A12") (pinfunction "GND_A12") (pintype "passive"))
      (node (ref "J1") (pin "B1") (pinfunction "GND_B1") (pintype "passive"))
      (node (ref "J1") (pin "B12") (pinfunction "GND_B12") (pintype "passive"))
      (node (ref "J1") (pin "MH1") (pinfunction "Tab_MH1") (pintype "passive"))
      (node (ref "J1") (pin "MH2") (pinfunction "Tab_MH2") (pintype "passive"))
      (node (ref "J1") (pin "MH3") (pinfunction "Tab_MH3") (pintype "passive"))
      (node (ref "J1") (pin "MH4") (pinfunction "Tab_MH4") (pintype "passive"))
      (node (ref "P1") (pin "2") (pinfunction "2_2") (pintype "passive"))
      (node (ref "R10") (pin "2") (pinfunction "2_2") (pintype "passive"))
      (node (ref "R11") (pin "2") (pinfunction "2_2") (pintype "passive"))
      (node (ref "R18") (pin "2") (pinfunction "2_2") (pintype "passive"))
      (node (ref "R3") (pin "2") (pinfunction "2_2") (pintype "passive"))
      (node (ref "R6") (pin "2") (pinfunction "2_2") (pintype "passive"))
      (node (ref "T1") (pin "2") (pinfunction "S_2") (pintype "passive"))
      (node (ref "U1") (pin "11") (pinfunction "GND_11") (pintype "power_in"))
      (node (ref "U1") (pin "15") (pinfunction "GND_15") (pintype "power_in"))
      (node (ref "U1") (pin "17") (pinfunction "EPAD_N.C._17") (pintype "passive"))
      (node (ref "U1") (pin "3") (pinfunction "GND_3") (pintype "power_in"))
      (node (ref "U2") (pin "2") (pinfunction "GND_2") (pintype "power_in"))
      (node (ref "U5") (pin "2") (pinfunction "LR_2") (pintype "input"))
      (node (ref "U5") (pin "3") (pinfunction "GND_3") (pintype "passive"))
      (node (ref "U6") (pin "29") (pinfunction "GND_29") (pintype "power_in"))
    )
    (net (code "38") (name "Net-(D1-K)") (class "Default")
      (node (ref "D1") (pin "2") (pinfunction "K_2") (pintype "passive"))
      (node (ref "R1") (pin "1") (pinfunction "1_1") (pintype "passive"))
    )
    (net (code "39") (name "Net-(D2-K)") (class "Default")
      (node (ref "D2") (pin "2") (pinfunction "K_2") (pintype "passive"))
      (node (ref "R5") (pin "1") (pinfunction "1_1") (pintype "passive"))
    )
    (net (code "40") (name "Net-(D3-K)") (class "Default")
      (node (ref "D3") (pin "2") (pinfunction "K_2") (pintype "passive"))
      (node (ref "R12") (pin "1") (pinfunction "1_1") (pintype "passive"))
    )
    (net (code "41") (name "Net-(D4-K)") (class "Default")
      (node (ref "D4") (pin "2") (pinfunction "K_2") (pintype "passive"))
      (node (ref "R13") (pin "1") (pinfunction "1_1") (pintype "passive"))
    )
    (net (code "42") (name "Net-(D5-K)") (class "Default")
      (node (ref "D5") (pin "2") (pinfunction "K_2") (pintype "passive"))
      (node (ref "R14") (pin "1") (pinfunction "1_1") (pintype "passive"))
    )
    (net (code "43") (name "Net-(D6-K)") (class "Default")
      (node (ref "D6") (pin "2") (pinfunction "K_2") (pintype "passive"))
      (node (ref "R15") (pin "1") (pinfunction "1_1") (pintype "passive"))
    )
    (net (code "44") (name "Net-(D7-K)") (class "Default")
      (node (ref "D7") (pin "2") (pinfunction "K_2") (pintype "passive"))
      (node (ref "R16") (pin "1") (pinfunction "1_1") (pintype "passive"))
    )
    (net (code "45") (name "Net-(D8-K)") (class "Default")
      (node (ref "D8") (pin "2") (pinfunction "K_2") (pintype "passive"))
      (node (ref "R17") (pin "1") (pinfunction "1_1") (pintype "passive"))
    )
    (net (code "46") (name "Net-(R7-Pad2)") (class "Default")
      (node (ref "R7") (pin "2") (pinfunction "2_2") (pintype "passive"))
      (node (ref "SW2") (pin "1") (pinfunction "1_1") (pintype "passive"))
    )
    (net (code "47") (name "Net-(T1-D)") (class "Default")
      (node (ref "R1") (pin "2") (pinfunction "2_2") (pintype "passive"))
      (node (ref "R12") (pin "2") (pinfunction "2_2") (pintype "passive"))
      (node (ref "R13") (pin "2") (pinfunction "2_2") (pintype "passive"))
      (node (ref "R14") (pin "2") (pinfunction "2_2") (pintype "passive"))
      (node (ref "R15") (pin "2") (pinfunction "2_2") (pintype "passive"))
      (node (ref "R16") (pin "2") (pinfunction "2_2") (pintype "passive"))
      (node (ref "R17") (pin "2") (pinfunction "2_2") (pintype "passive"))
      (node (ref "R5") (pin "2") (pinfunction "2_2") (pintype "passive"))
      (node (ref "T1") (pin "3") (pinfunction "D_3") (pintype "passive"))
    )
    (net (code "48") (name "Net-(U1-GAIN)") (class "Default")
      (node (ref "R2") (pin "1") (pinfunction "1_1") (pintype "passive"))
      (node (ref "R3") (pin "1") (pinfunction "1_1") (pintype "passive"))
      (node (ref "U1") (pin "2") (pinfunction "GAIN_2") (pintype "input"))
    )
    (net (code "49") (name "Net-(U1-OUTN)") (class "Default")
      (node (ref "F2") (pin "1") (pinfunction "1_1") (pintype "passive"))
      (node (ref "U1") (pin "10") (pinfunction "OUTN_10") (pintype "output"))
    )
    (net (code "50") (name "Net-(U1-OUTP)") (class "Default")
      (node (ref "F1") (pin "1") (pinfunction "1_1") (pintype "passive"))
      (node (ref "U1") (pin "9") (pinfunction "OUTP_9") (pintype "output"))
    )
    (net (code "51") (name "VSYS") (class "Default")
      (node (ref "C1") (pin "1") (pinfunction "1_1") (pintype "passive"))
      (node (ref "C2") (pin "1") (pinfunction "1_1") (pintype "passive"))
      (node (ref "D9") (pin "A") (pinfunction "A_A") (pintype "passive"))
      (node (ref "P1") (pin "12") (pinfunction "12_12") (pintype "passive"))
      (node (ref "R2") (pin "2") (pinfunction "2_2") (pintype "passive"))
      (node (ref "R4") (pin "1") (pinfunction "1_1") (pintype "passive"))
      (node (ref "U1") (pin "7") (pinfunction "VDD_7") (pintype "power_in"))
      (node (ref "U1") (pin "8") (pinfunction "VDD_8") (pintype "power_in"))
    )
    (net (code "52") (name "VUSB") (class "Default")
      (node (ref "C5") (pin "1") (pinfunction "1_1") (pintype "passive"))
      (node (ref "D1") (pin "1") (pinfunction "A_1") (pintype "passive"))
      (node (ref "D2") (pin "1") (pinfunction "A_1") (pintype "passive"))
      (node (ref "D3") (pin "1") (pinfunction "A_1") (pintype "passive"))
      (node (ref "D4") (pin "1") (pinfunction "A_1") (pintype "passive"))
      (node (ref "D5") (pin "1") (pinfunction "A_1") (pintype "passive"))
      (node (ref "D6") (pin "1") (pinfunction "A_1") (pintype "passive"))
      (node (ref "D7") (pin "1") (pinfunction "A_1") (pintype "passive"))
      (node (ref "D8") (pin "1") (pinfunction "A_1") (pintype "passive"))
      (node (ref "D9") (pin "C") (pinfunction "C_C") (pintype "passive"))
      (node (ref "J1") (pin "A4") (pinfunction "VBUS_A4") (pintype "passive"))
      (node (ref "J1") (pin "A9") (pinfunction "VBUS_A9") (pintype "passive"))
      (node (ref "J1") (pin "B4") (pinfunction "VBUS_B4") (pintype "passive"))
      (node (ref "J1") (pin "B9") (pinfunction "VBUS_B9") (pintype "passive"))
      (node (ref "U2") (pin "1") (pinfunction "VIN_1") (pintype "power_in"))
      (node (ref "U2") (pin "3") (pinfunction "CE_3") (pintype "input"))
    )
    (net (code "53") (name "unconnected-(J1-SBU1-PadA8)") (class "Default")
      (node (ref "J1") (pin "A8") (pinfunction "SBU1_A8") (pintype "passive+no_connect"))
    )
    (net (code "54") (name "unconnected-(J1-SBU2-PadB8)") (class "Default")
      (node (ref "J1") (pin "B8") (pinfunction "SBU2_B8") (pintype "passive+no_connect"))
    )
    (net (code "55") (name "unconnected-(U1-N.C.-Pad5)") (class "Default")
      (node (ref "U1") (pin "5") (pinfunction "N.C._5") (pintype "passive+no_connect"))
    )
    (net (code "56") (name "unconnected-(U1-N.C.-Pad6)") (class "Default")
      (node (ref "U1") (pin "6") (pinfunction "N.C._6") (pintype "passive+no_connect"))
    )
    (net (code "57") (name "unconnected-(U1-N.C.-Pad12)") (class "Default")
      (node (ref "U1") (pin "12") (pinfunction "N.C._12") (pintype "passive+no_connect"))
    )
    (net (code "58") (name "unconnected-(U1-N.C.-Pad13)") (class "Default")
      (node (ref "U1") (pin "13") (pinfunction "N.C._13") (pintype "passive+no_connect"))
    )
    (net (code "59") (name "unconnected-(U2-N.C.-Pad4)") (class "Default")
      (node (ref "U2") (pin "4") (pinfunction "N.C._4") (pintype "passive+no_connect"))
    )
  )
)
